# LPC_2TE_3_8smd.net
KiCad netlist of a schematic drawn in EAGLE
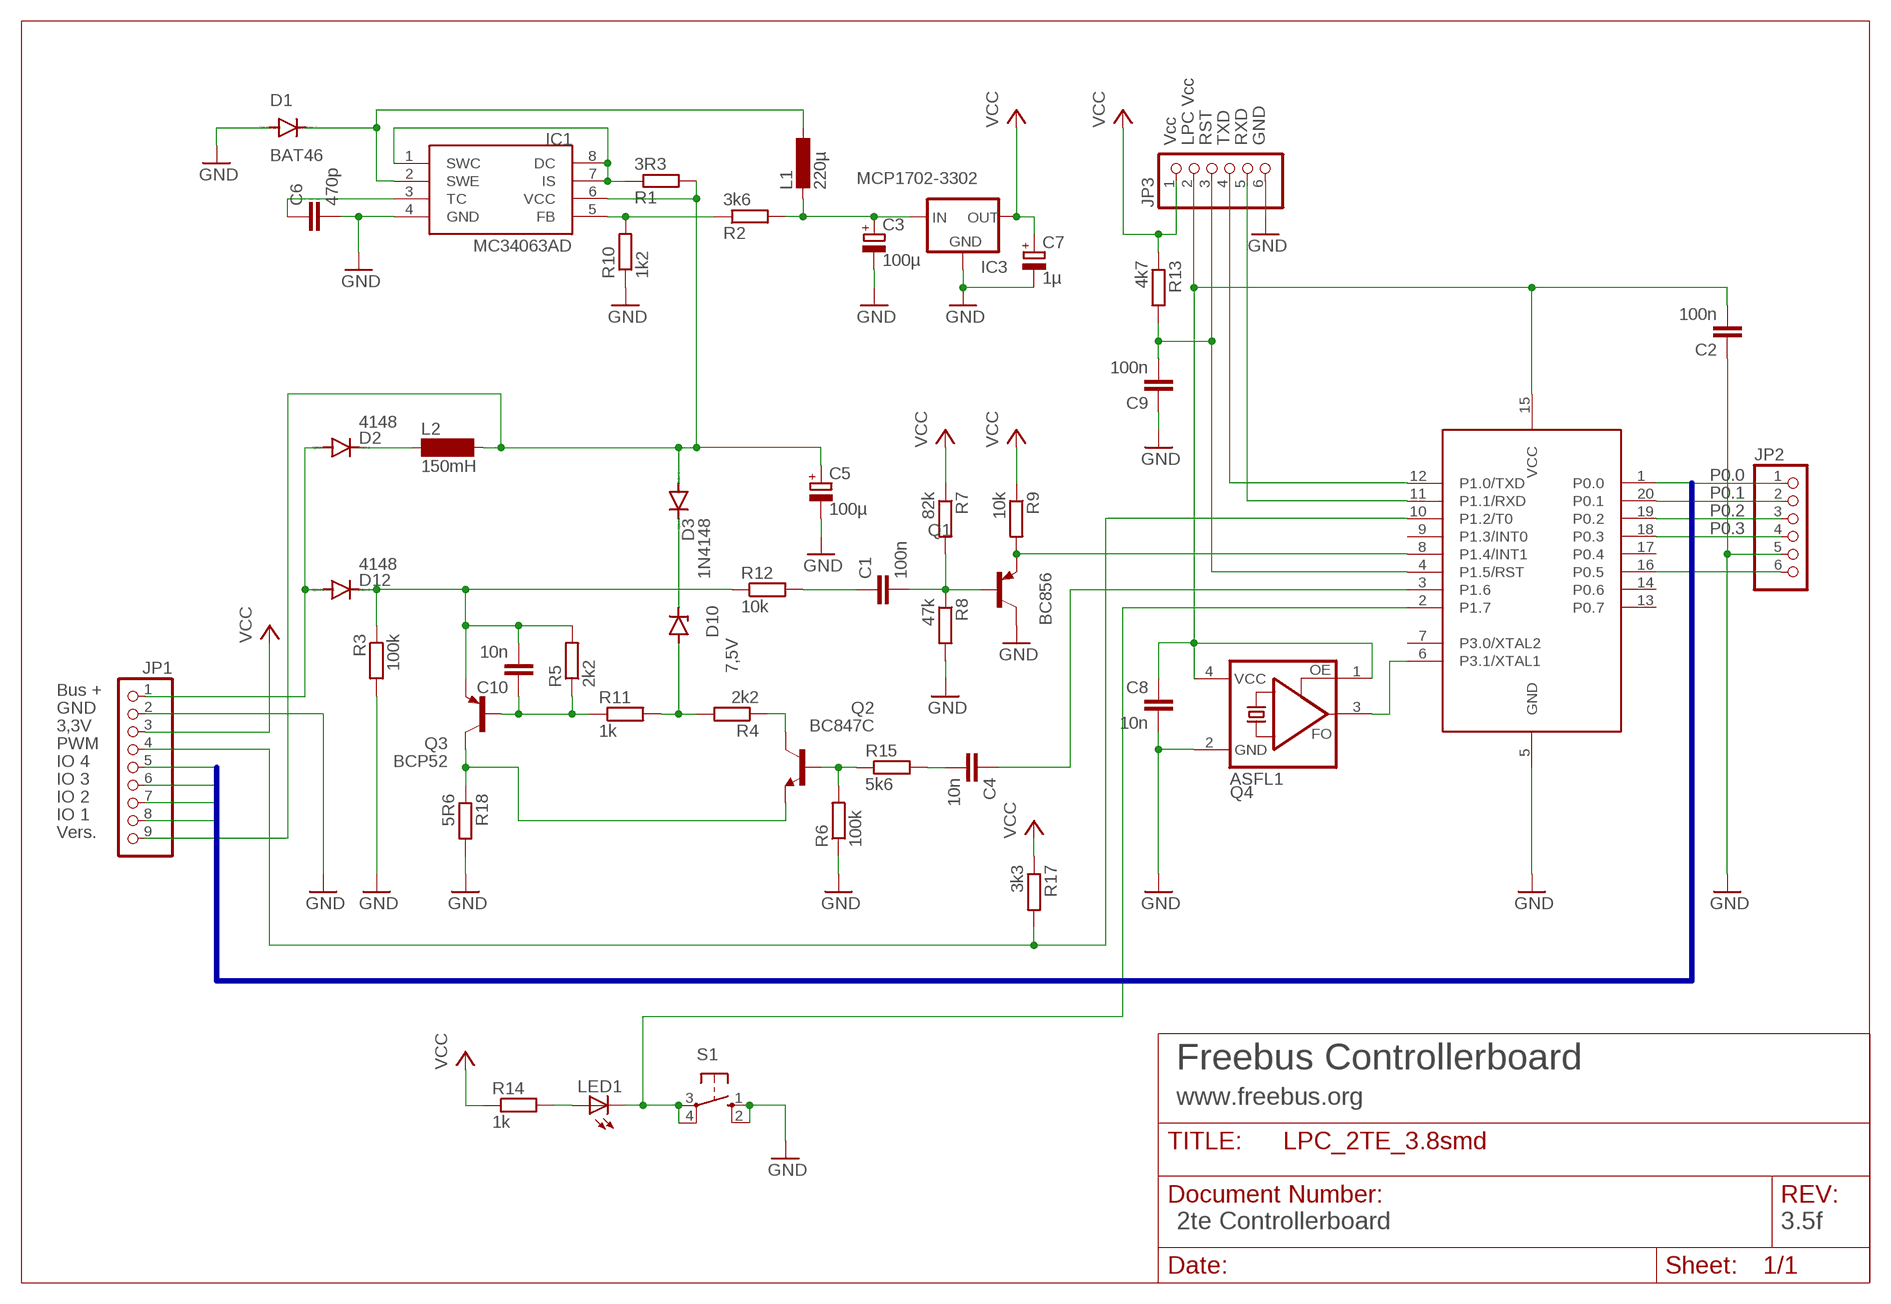
[diagram p0: schematic, sheet 1]

(export (version "E")
  (design (tool "Eeschema 10.0.6"))
  (components
    (comp (ref "89LPC922")
      (value "89LPC922")
      (footprint "eagle-import:DIL20")
      (libsource (lib "eagle-import") (part "89LPC922"))
    )
    (comp (ref "C1")
      (value "100n")
      (footprint "eagle-import:C1206")
      (libsource (lib "eagle-import") (part "C-EUC1206"))
    )
    (comp (ref "C2")
      (value "100n")
      (footprint "eagle-import:C1206")
      (libsource (lib "eagle-import") (part "C-EUC1206"))
    )
    (comp (ref "C3")
      (value "100µ")
      (footprint "eagle-import:E2,5-6")
      (libsource (lib "eagle-import") (part "CPOL-EUE2.5-6"))
    )
    (comp (ref "C4")
      (value "10n")
      (footprint "eagle-import:C1206")
      (libsource (lib "eagle-import") (part "C-EUC1206"))
    )
    (comp (ref "C5")
      (value "100µ")
      (footprint "eagle-import:E3,5-8")
      (libsource (lib "eagle-import") (part "CPOL-EUE3.5-8"))
    )
    (comp (ref "C6")
      (value "470p")
      (footprint "eagle-import:C1206")
      (libsource (lib "eagle-import") (part "C-EUC1206"))
    )
    (comp (ref "C7")
      (value "1µ")
      (footprint "eagle-import:E2-5")
      (libsource (lib "eagle-import") (part "CPOL-EUE2-5"))
    )
    (comp (ref "C8")
      (value "10n")
      (footprint "eagle-import:C1206")
      (libsource (lib "eagle-import") (part "C-EUC1206"))
    )
    (comp (ref "C9")
      (value "100n")
      (footprint "eagle-import:C1206")
      (libsource (lib "eagle-import") (part "C-EUC1206"))
    )
    (comp (ref "C10")
      (value "10n")
      (footprint "eagle-import:C1206")
      (libsource (lib "eagle-import") (part "C-EUC1206"))
    )
    (comp (ref "D1")
      (value "BAT46")
      (footprint "eagle-import:MINIMELF")
      (libsource (lib "eagle-import") (part "DIODE-MINIMELF"))
    )
    (comp (ref "D2")
      (value "4148")
      (footprint "eagle-import:MINIMELF")
      (libsource (lib "eagle-import") (part "DIODE-MINIMELF"))
    )
    (comp (ref "D3")
      (value "1N4148")
      (footprint "eagle-import:MINIMELF")
      (libsource (lib "eagle-import") (part "DIODE-MINIMELF"))
    )
    (comp (ref "D10")
      (value "7,5V")
      (footprint "eagle-import:DO35Z10")
      (libsource (lib "eagle-import") (part "ZPD"))
    )
    (comp (ref "D12")
      (value "4148")
      (footprint "eagle-import:MINIMELF")
      (libsource (lib "eagle-import") (part "DIODE-MINIMELF"))
    )
    (comp (ref "IC1")
      (value "MC34063AD")
      (footprint "eagle-import:SOIC8")
      (libsource (lib "eagle-import") (part "MC34063AD"))
    )
    (comp (ref "IC3")
      (value "MCP1702-3302")
      (footprint "eagle-import:79LXX")
      (libsource (lib "eagle-import") (part "79LXX"))
    )
    (comp (ref "JP1")
      (value "PINHD-1X9_LONG_2.54")
      (footprint "eagle-import:1X09_LONG")
      (libsource (lib "eagle-import") (part "PINHD-1X9_LONG_2.54"))
    )
    (comp (ref "JP2")
      (value "PINHD-1X6")
      (footprint "eagle-import:1X06")
      (libsource (lib "eagle-import") (part "PINHD-1X6"))
    )
    (comp (ref "JP3")
      (value "PINHD-1X6")
      (footprint "eagle-import:1X06")
      (libsource (lib "eagle-import") (part "PINHD-1X6"))
    )
    (comp (ref "L1")
      (value "220µ")
      (footprint "eagle-import:0207_12")
      (libsource (lib "eagle-import") (part "L-EU0207/12"))
    )
    (comp (ref "L2")
      (value "150mH")
      (footprint "eagle-import:BS11")
      (libsource (lib "eagle-import") (part "BS11"))
    )
    (comp (ref "LED1")
      (value "LED3MM")
      (footprint "eagle-import:LED3MM")
      (libsource (lib "eagle-import") (part "LED3MM"))
    )
    (comp (ref "Q1")
      (value "BC856")
      (footprint "eagle-import:SOT23-BEC")
      (libsource (lib "eagle-import") (part "BC856SMDB"))
    )
    (comp (ref "Q2")
      (value "BC847C")
      (footprint "eagle-import:SOT23")
      (libsource (lib "eagle-import") (part "BC847SMDC"))
    )
    (comp (ref "Q3")
      (value "BCP52")
      (footprint "eagle-import:SOT223")
      (libsource (lib "eagle-import") (part "FZT753SMD"))
    )
    (comp (ref "Q4")
      (value "ASFL1")
      (footprint "eagle-import:ASF")
      (fields (field (name "MF") "Abracon Corporation") (field (name "MPN") "ASFL1-125.000MHZ-EC-T"))
      (libsource (lib "eagle-import") (part "ASFL1"))
    )
    (comp (ref "R1")
      (value "3R3")
      (footprint "eagle-import:R1206")
      (libsource (lib "eagle-import") (part "R-EU_R1206"))
    )
    (comp (ref "R2")
      (value "3k6")
      (footprint "eagle-import:R1206")
      (libsource (lib "eagle-import") (part "R-EU_R1206"))
    )
    (comp (ref "R3")
      (value "100k")
      (footprint "eagle-import:R1206")
      (libsource (lib "eagle-import") (part "R-EU_R1206"))
    )
    (comp (ref "R4")
      (value "2k2")
      (footprint "eagle-import:R1206")
      (libsource (lib "eagle-import") (part "R-EU_R1206"))
    )
    (comp (ref "R5")
      (value "2k2")
      (footprint "eagle-import:R1206")
      (libsource (lib "eagle-import") (part "R-EU_R1206"))
    )
    (comp (ref "R6")
      (value "100k")
      (footprint "eagle-import:R1206")
      (libsource (lib "eagle-import") (part "R-EU_R1206"))
    )
    (comp (ref "R7")
      (value "82k")
      (footprint "eagle-import:R1206")
      (libsource (lib "eagle-import") (part "R-EU_R1206"))
    )
    (comp (ref "R8")
      (value "47k")
      (footprint "eagle-import:R1206")
      (libsource (lib "eagle-import") (part "R-EU_R1206"))
    )
    (comp (ref "R9")
      (value "10k")
      (footprint "eagle-import:R1206")
      (libsource (lib "eagle-import") (part "R-EU_R1206"))
    )
    (comp (ref "R10")
      (value "1k2")
      (footprint "eagle-import:R1206")
      (libsource (lib "eagle-import") (part "R-EU_R1206"))
    )
    (comp (ref "R11")
      (value "1k")
      (footprint "eagle-import:R1206")
      (libsource (lib "eagle-import") (part "R-EU_R1206"))
    )
    (comp (ref "R12")
      (value "10k")
      (footprint "eagle-import:R1206")
      (libsource (lib "eagle-import") (part "R-EU_R1206"))
    )
    (comp (ref "R13")
      (value "4k7")
      (footprint "eagle-import:R1206")
      (libsource (lib "eagle-import") (part "R-EU_R1206"))
    )
    (comp (ref "R14")
      (value "1k")
      (footprint "eagle-import:R1206")
      (libsource (lib "eagle-import") (part "R-EU_R1206"))
    )
    (comp (ref "R15")
      (value "5k6")
      (footprint "eagle-import:R1206")
      (libsource (lib "eagle-import") (part "R-EU_R1206"))
    )
    (comp (ref "R17")
      (value "3k3")
      (footprint "eagle-import:R1206")
      (libsource (lib "eagle-import") (part "R-EU_R1206"))
    )
    (comp (ref "R18")
      (value "5R6")
      (footprint "eagle-import:R1206")
      (libsource (lib "eagle-import") (part "R-EU_R1206"))
    )
    (comp (ref "S1")
      (value "10-XX")
      (footprint "eagle-import:B3F-10XX")
      (libsource (lib "eagle-import") (part "10-XX"))
    )
  )
  (nets
    (net (code "1") (name "/P0.0") (class "Default")
      (node (ref "89LPC922") (pin "1") (pinfunction "P0.0_1") (pintype "bidirectional"))
      (node (ref "JP1") (pin "8") (pinfunction "8_8") (pintype "passive"))
      (node (ref "JP2") (pin "1") (pinfunction "1_1") (pintype "passive"))
    )
    (net (code "2") (name "/P0.1") (class "Default")
      (node (ref "89LPC922") (pin "20") (pinfunction "P0.1_20") (pintype "bidirectional"))
      (node (ref "JP1") (pin "7") (pinfunction "7_7") (pintype "passive"))
      (node (ref "JP2") (pin "2") (pinfunction "2_2") (pintype "passive"))
    )
    (net (code "3") (name "/P0.2") (class "Default")
      (node (ref "89LPC922") (pin "19") (pinfunction "P0.2_19") (pintype "bidirectional"))
      (node (ref "JP1") (pin "6") (pinfunction "6_6") (pintype "passive"))
      (node (ref "JP2") (pin "3") (pinfunction "3_3") (pintype "passive"))
    )
    (net (code "4") (name "/P0.3") (class "Default")
      (node (ref "89LPC922") (pin "18") (pinfunction "P0.3_18") (pintype "bidirectional"))
      (node (ref "JP1") (pin "5") (pinfunction "5_5") (pintype "passive"))
      (node (ref "JP2") (pin "4") (pinfunction "4_4") (pintype "passive"))
    )
    (net (code "5") (name "GND") (class "Default")
      (node (ref "89LPC922") (pin "5") (pinfunction "GND_5") (pintype "bidirectional"))
      (node (ref "C2") (pin "1") (pinfunction "1_1") (pintype "passive"))
      (node (ref "C3") (pin "-") (pinfunction "-_-") (pintype "passive"))
      (node (ref "C5") (pin "-") (pinfunction "-_-") (pintype "passive"))
      (node (ref "C6") (pin "2") (pinfunction "2_2") (pintype "passive"))
      (node (ref "C7") (pin "-") (pinfunction "-_-") (pintype "passive"))
      (node (ref "C8") (pin "2") (pinfunction "2_2") (pintype "passive"))
      (node (ref "C9") (pin "1") (pinfunction "1_1") (pintype "passive"))
      (node (ref "D1") (pin "A") (pinfunction "A_A") (pintype "passive"))
      (node (ref "IC1") (pin "4") (pinfunction "GND_4") (pintype "passive"))
      (node (ref "IC3") (pin "GND") (pinfunction "GND_GND") (pintype "input"))
      (node (ref "JP1") (pin "2") (pinfunction "2_2") (pintype "passive"))
      (node (ref "JP2") (pin "5") (pinfunction "5_5") (pintype "passive"))
      (node (ref "JP3") (pin "6") (pinfunction "6_6") (pintype "passive"))
      (node (ref "Q1") (pin "C") (pinfunction "C_C") (pintype "passive"))
      (node (ref "Q4") (pin "2") (pinfunction "GND_2") (pintype "power_in"))
      (node (ref "R10") (pin "1") (pinfunction "1_1") (pintype "passive"))
      (node (ref "R18") (pin "2") (pinfunction "2_2") (pintype "passive"))
      (node (ref "R3") (pin "2") (pinfunction "2_2") (pintype "passive"))
      (node (ref "R6") (pin "1") (pinfunction "1_1") (pintype "passive"))
      (node (ref "R8") (pin "2") (pinfunction "2_2") (pintype "passive"))
      (node (ref "S1") (pin "1") (pinfunction "S_1") (pintype "passive"))
      (node (ref "S1") (pin "2") (pinfunction "S1_2") (pintype "passive"))
    )
    (net (code "6") (name "Net-(89LPC922-P0.5)") (class "Default")
      (node (ref "89LPC922") (pin "16") (pinfunction "P0.5_16") (pintype "bidirectional"))
      (node (ref "JP2") (pin "6") (pinfunction "6_6") (pintype "passive"))
    )
    (net (code "7") (name "Net-(89LPC922-P1.0{slash}TXD)") (class "Default")
      (node (ref "89LPC922") (pin "12") (pinfunction "P1.0/TXD_12") (pintype "bidirectional"))
      (node (ref "JP3") (pin "4") (pinfunction "4_4") (pintype "passive"))
    )
    (net (code "8") (name "Net-(89LPC922-P1.1{slash}RXD)") (class "Default")
      (node (ref "89LPC922") (pin "11") (pinfunction "P1.1/RXD_11") (pintype "bidirectional"))
      (node (ref "JP3") (pin "5") (pinfunction "5_5") (pintype "passive"))
    )
    (net (code "9") (name "Net-(89LPC922-P1.2{slash}T0)") (class "Default")
      (node (ref "89LPC922") (pin "10") (pinfunction "P1.2/T0_10") (pintype "bidirectional"))
      (node (ref "JP1") (pin "4") (pinfunction "4_4") (pintype "passive"))
      (node (ref "R17") (pin "2") (pinfunction "2_2") (pintype "passive"))
    )
    (net (code "10") (name "Net-(89LPC922-P1.4{slash}INT1)") (class "Default")
      (node (ref "89LPC922") (pin "8") (pinfunction "P1.4/INT1_8") (pintype "bidirectional"))
      (node (ref "Q1") (pin "E") (pinfunction "E_E") (pintype "passive"))
      (node (ref "R9") (pin "2") (pinfunction "2_2") (pintype "passive"))
    )
    (net (code "11") (name "Net-(89LPC922-P1.5{slash}RST)") (class "Default")
      (node (ref "89LPC922") (pin "4") (pinfunction "P1.5/RST_4") (pintype "bidirectional"))
      (node (ref "C9") (pin "2") (pinfunction "2_2") (pintype "passive"))
      (node (ref "JP3") (pin "3") (pinfunction "3_3") (pintype "passive"))
      (node (ref "R13") (pin "2") (pinfunction "2_2") (pintype "passive"))
    )
    (net (code "12") (name "Net-(89LPC922-P1.6)") (class "Default")
      (node (ref "89LPC922") (pin "3") (pinfunction "P1.6_3") (pintype "bidirectional"))
      (node (ref "C4") (pin "1") (pinfunction "1_1") (pintype "passive"))
    )
    (net (code "13") (name "Net-(89LPC922-P1.7)") (class "Default")
      (node (ref "89LPC922") (pin "2") (pinfunction "P1.7_2") (pintype "bidirectional"))
      (node (ref "LED1") (pin "K") (pinfunction "C_K") (pintype "passive"))
      (node (ref "S1") (pin "3") (pinfunction "P_3") (pintype "passive"))
      (node (ref "S1") (pin "4") (pinfunction "P1_4") (pintype "passive"))
    )
    (net (code "14") (name "Net-(89LPC922-P3.1{slash}XTAL1)") (class "Default")
      (node (ref "89LPC922") (pin "6") (pinfunction "P3.1/XTAL1_6") (pintype "bidirectional"))
      (node (ref "Q4") (pin "3") (pinfunction "FO_3") (pintype "output"))
    )
    (net (code "15") (name "Net-(89LPC922-VCC)") (class "Default")
      (node (ref "89LPC922") (pin "15") (pinfunction "VCC_15") (pintype "bidirectional"))
      (node (ref "C2") (pin "2") (pinfunction "2_2") (pintype "passive"))
      (node (ref "C8") (pin "1") (pinfunction "1_1") (pintype "passive"))
      (node (ref "JP3") (pin "2") (pinfunction "2_2") (pintype "passive"))
      (node (ref "Q4") (pin "1") (pinfunction "OE_1") (pintype "input"))
      (node (ref "Q4") (pin "4") (pinfunction "VCC_4") (pintype "power_in"))
    )
    (net (code "16") (name "Net-(C1-Pad1)") (class "Default")
      (node (ref "C1") (pin "1") (pinfunction "1_1") (pintype "passive"))
      (node (ref "R12") (pin "2") (pinfunction "2_2") (pintype "passive"))
    )
    (net (code "17") (name "Net-(C1-Pad2)") (class "Default")
      (node (ref "C1") (pin "2") (pinfunction "2_2") (pintype "passive"))
      (node (ref "Q1") (pin "B") (pinfunction "B_B") (pintype "passive"))
      (node (ref "R7") (pin "2") (pinfunction "2_2") (pintype "passive"))
      (node (ref "R8") (pin "1") (pinfunction "1_1") (pintype "passive"))
    )
    (net (code "18") (name "Net-(C3-Pad+)") (class "Default")
      (node (ref "C3") (pin "+") (pinfunction "+_+") (pintype "passive"))
      (node (ref "IC3") (pin "IN") (pinfunction "IN_IN") (pintype "input"))
      (node (ref "L1") (pin "2") (pinfunction "2_2") (pintype "passive"))
      (node (ref "R2") (pin "2") (pinfunction "2_2") (pintype "passive"))
    )
    (net (code "19") (name "Net-(C4-Pad2)") (class "Default")
      (node (ref "C4") (pin "2") (pinfunction "2_2") (pintype "passive"))
      (node (ref "R15") (pin "2") (pinfunction "2_2") (pintype "passive"))
    )
    (net (code "20") (name "Net-(D2-PadC)") (class "Default")
      (node (ref "D2") (pin "C") (pinfunction "C_C") (pintype "passive"))
      (node (ref "L2") (pin "1") (pinfunction "1_1") (pintype "passive"))
    )
    (net (code "21") (name "Net-(D10-PadA)") (class "Default")
      (node (ref "D10") (pin "A") (pinfunction "A_A") (pintype "passive"))
      (node (ref "R11") (pin "2") (pinfunction "2_2") (pintype "passive"))
      (node (ref "R4") (pin "2") (pinfunction "2_2") (pintype "passive"))
    )
    (net (code "22") (name "Net-(D10-PadC)") (class "Default")
      (node (ref "D10") (pin "C") (pinfunction "C_C") (pintype "passive"))
      (node (ref "D3") (pin "C") (pinfunction "C_C") (pintype "passive"))
    )
    (net (code "23") (name "Net-(D12-PadA)") (class "Default")
      (node (ref "D12") (pin "A") (pinfunction "A_A") (pintype "passive"))
      (node (ref "D2") (pin "A") (pinfunction "A_A") (pintype "passive"))
      (node (ref "JP1") (pin "1") (pinfunction "1_1") (pintype "passive"))
    )
    (net (code "24") (name "Net-(IC1-DC)") (class "Default")
      (node (ref "IC1") (pin "1") (pinfunction "SWC_1") (pintype "passive"))
      (node (ref "IC1") (pin "7") (pinfunction "IS_7") (pintype "passive"))
      (node (ref "IC1") (pin "8") (pinfunction "DC_8") (pintype "passive"))
      (node (ref "R1") (pin "1") (pinfunction "1_1") (pintype "passive"))
    )
    (net (code "25") (name "Net-(IC1-FB)") (class "Default")
      (node (ref "IC1") (pin "5") (pinfunction "FB_5") (pintype "passive"))
      (node (ref "R10") (pin "2") (pinfunction "2_2") (pintype "passive"))
      (node (ref "R2") (pin "1") (pinfunction "1_1") (pintype "passive"))
    )
    (net (code "26") (name "Net-(IC1-SWE)") (class "Default")
      (node (ref "D1") (pin "C") (pinfunction "C_C") (pintype "passive"))
      (node (ref "IC1") (pin "2") (pinfunction "SWE_2") (pintype "passive"))
      (node (ref "L1") (pin "1") (pinfunction "1_1") (pintype "passive"))
    )
    (net (code "27") (name "Net-(IC1-TC)") (class "Default")
      (node (ref "C6") (pin "1") (pinfunction "1_1") (pintype "passive"))
      (node (ref "IC1") (pin "3") (pinfunction "TC_3") (pintype "passive"))
    )
    (net (code "28") (name "Net-(IC1-VCC)") (class "Default")
      (node (ref "C5") (pin "+") (pinfunction "+_+") (pintype "passive"))
      (node (ref "D3") (pin "A") (pinfunction "A_A") (pintype "passive"))
      (node (ref "IC1") (pin "6") (pinfunction "VCC_6") (pintype "passive"))
      (node (ref "JP1") (pin "9") (pinfunction "9_9") (pintype "passive"))
      (node (ref "L2") (pin "2") (pinfunction "2_2") (pintype "passive"))
      (node (ref "R1") (pin "2") (pinfunction "2_2") (pintype "passive"))
    )
    (net (code "29") (name "Net-(LED1-PadA)") (class "Default")
      (node (ref "LED1") (pin "A") (pinfunction "A_A") (pintype "passive"))
      (node (ref "R14") (pin "2") (pinfunction "2_2") (pintype "passive"))
    )
    (net (code "30") (name "Net-(Q2-B)") (class "Default")
      (node (ref "Q2") (pin "1") (pinfunction "B_1") (pintype "passive"))
      (node (ref "R15") (pin "1") (pinfunction "1_1") (pintype "passive"))
      (node (ref "R6") (pin "2") (pinfunction "2_2") (pintype "passive"))
    )
    (net (code "31") (name "Net-(Q2-C)") (class "Default")
      (node (ref "Q2") (pin "3") (pinfunction "C_3") (pintype "passive"))
      (node (ref "R4") (pin "1") (pinfunction "1_1") (pintype "passive"))
    )
    (net (code "32") (name "Net-(Q2-E)") (class "Default")
      (node (ref "Q2") (pin "2") (pinfunction "E_2") (pintype "passive"))
      (node (ref "Q3") (pin "2") (pinfunction "C_2") (pintype "passive"))
      (node (ref "Q3") (pin "4") (pinfunction "C_4") (pintype "passive"))
      (node (ref "R18") (pin "1") (pinfunction "1_1") (pintype "passive"))
    )
    (net (code "33") (name "Net-(Q3-B)") (class "Default")
      (node (ref "C10") (pin "1") (pinfunction "1_1") (pintype "passive"))
      (node (ref "Q3") (pin "1") (pinfunction "B_1") (pintype "passive"))
      (node (ref "R11") (pin "1") (pinfunction "1_1") (pintype "passive"))
      (node (ref "R5") (pin "1") (pinfunction "1_1") (pintype "passive"))
    )
    (net (code "34") (name "Net-(Q3-E)") (class "Default")
      (node (ref "C10") (pin "2") (pinfunction "2_2") (pintype "passive"))
      (node (ref "D12") (pin "C") (pinfunction "C_C") (pintype "passive"))
      (node (ref "Q3") (pin "3") (pinfunction "E_3") (pintype "passive"))
      (node (ref "R12") (pin "1") (pinfunction "1_1") (pintype "passive"))
      (node (ref "R3") (pin "1") (pinfunction "1_1") (pintype "passive"))
      (node (ref "R5") (pin "2") (pinfunction "2_2") (pintype "passive"))
    )
    (net (code "35") (name "VCC") (class "Default")
      (node (ref "C7") (pin "+") (pinfunction "+_+") (pintype "passive"))
      (node (ref "IC3") (pin "OUT") (pinfunction "OUT_OUT") (pintype "passive"))
      (node (ref "JP1") (pin "3") (pinfunction "3_3") (pintype "passive"))
      (node (ref "JP3") (pin "1") (pinfunction "1_1") (pintype "passive"))
      (node (ref "R13") (pin "1") (pinfunction "1_1") (pintype "passive"))
      (node (ref "R14") (pin "1") (pinfunction "1_1") (pintype "passive"))
      (node (ref "R17") (pin "1") (pinfunction "1_1") (pintype "passive"))
      (node (ref "R7") (pin "1") (pinfunction "1_1") (pintype "passive"))
      (node (ref "R9") (pin "1") (pinfunction "1_1") (pintype "passive"))
    )
    (net (code "36") (name "unconnected-(89LPC922-P0.4-Pad17)") (class "Default")
      (node (ref "89LPC922") (pin "17") (pinfunction "P0.4_17") (pintype "bidirectional"))
    )
    (net (code "37") (name "unconnected-(89LPC922-P0.6-Pad14)") (class "Default")
      (node (ref "89LPC922") (pin "14") (pinfunction "P0.6_14") (pintype "bidirectional"))
    )
    (net (code "38") (name "unconnected-(89LPC922-P0.7-Pad13)") (class "Default")
      (node (ref "89LPC922") (pin "13") (pinfunction "P0.7_13") (pintype "bidirectional"))
    )
    (net (code "39") (name "unconnected-(89LPC922-P1.3{slash}INT0-Pad9)") (class "Default")
      (node (ref "89LPC922") (pin "9") (pinfunction "P1.3/INT0_9") (pintype "bidirectional"))
    )
    (net (code "40") (name "unconnected-(89LPC922-P3.0{slash}XTAL2-Pad7)") (class "Default")
      (node (ref "89LPC922") (pin "7") (pinfunction "P3.0/XTAL2_7") (pintype "bidirectional"))
    )
  )
)
